# FPGA_IO.net
KiCad netlist of a schematic drawn in Altium Designer
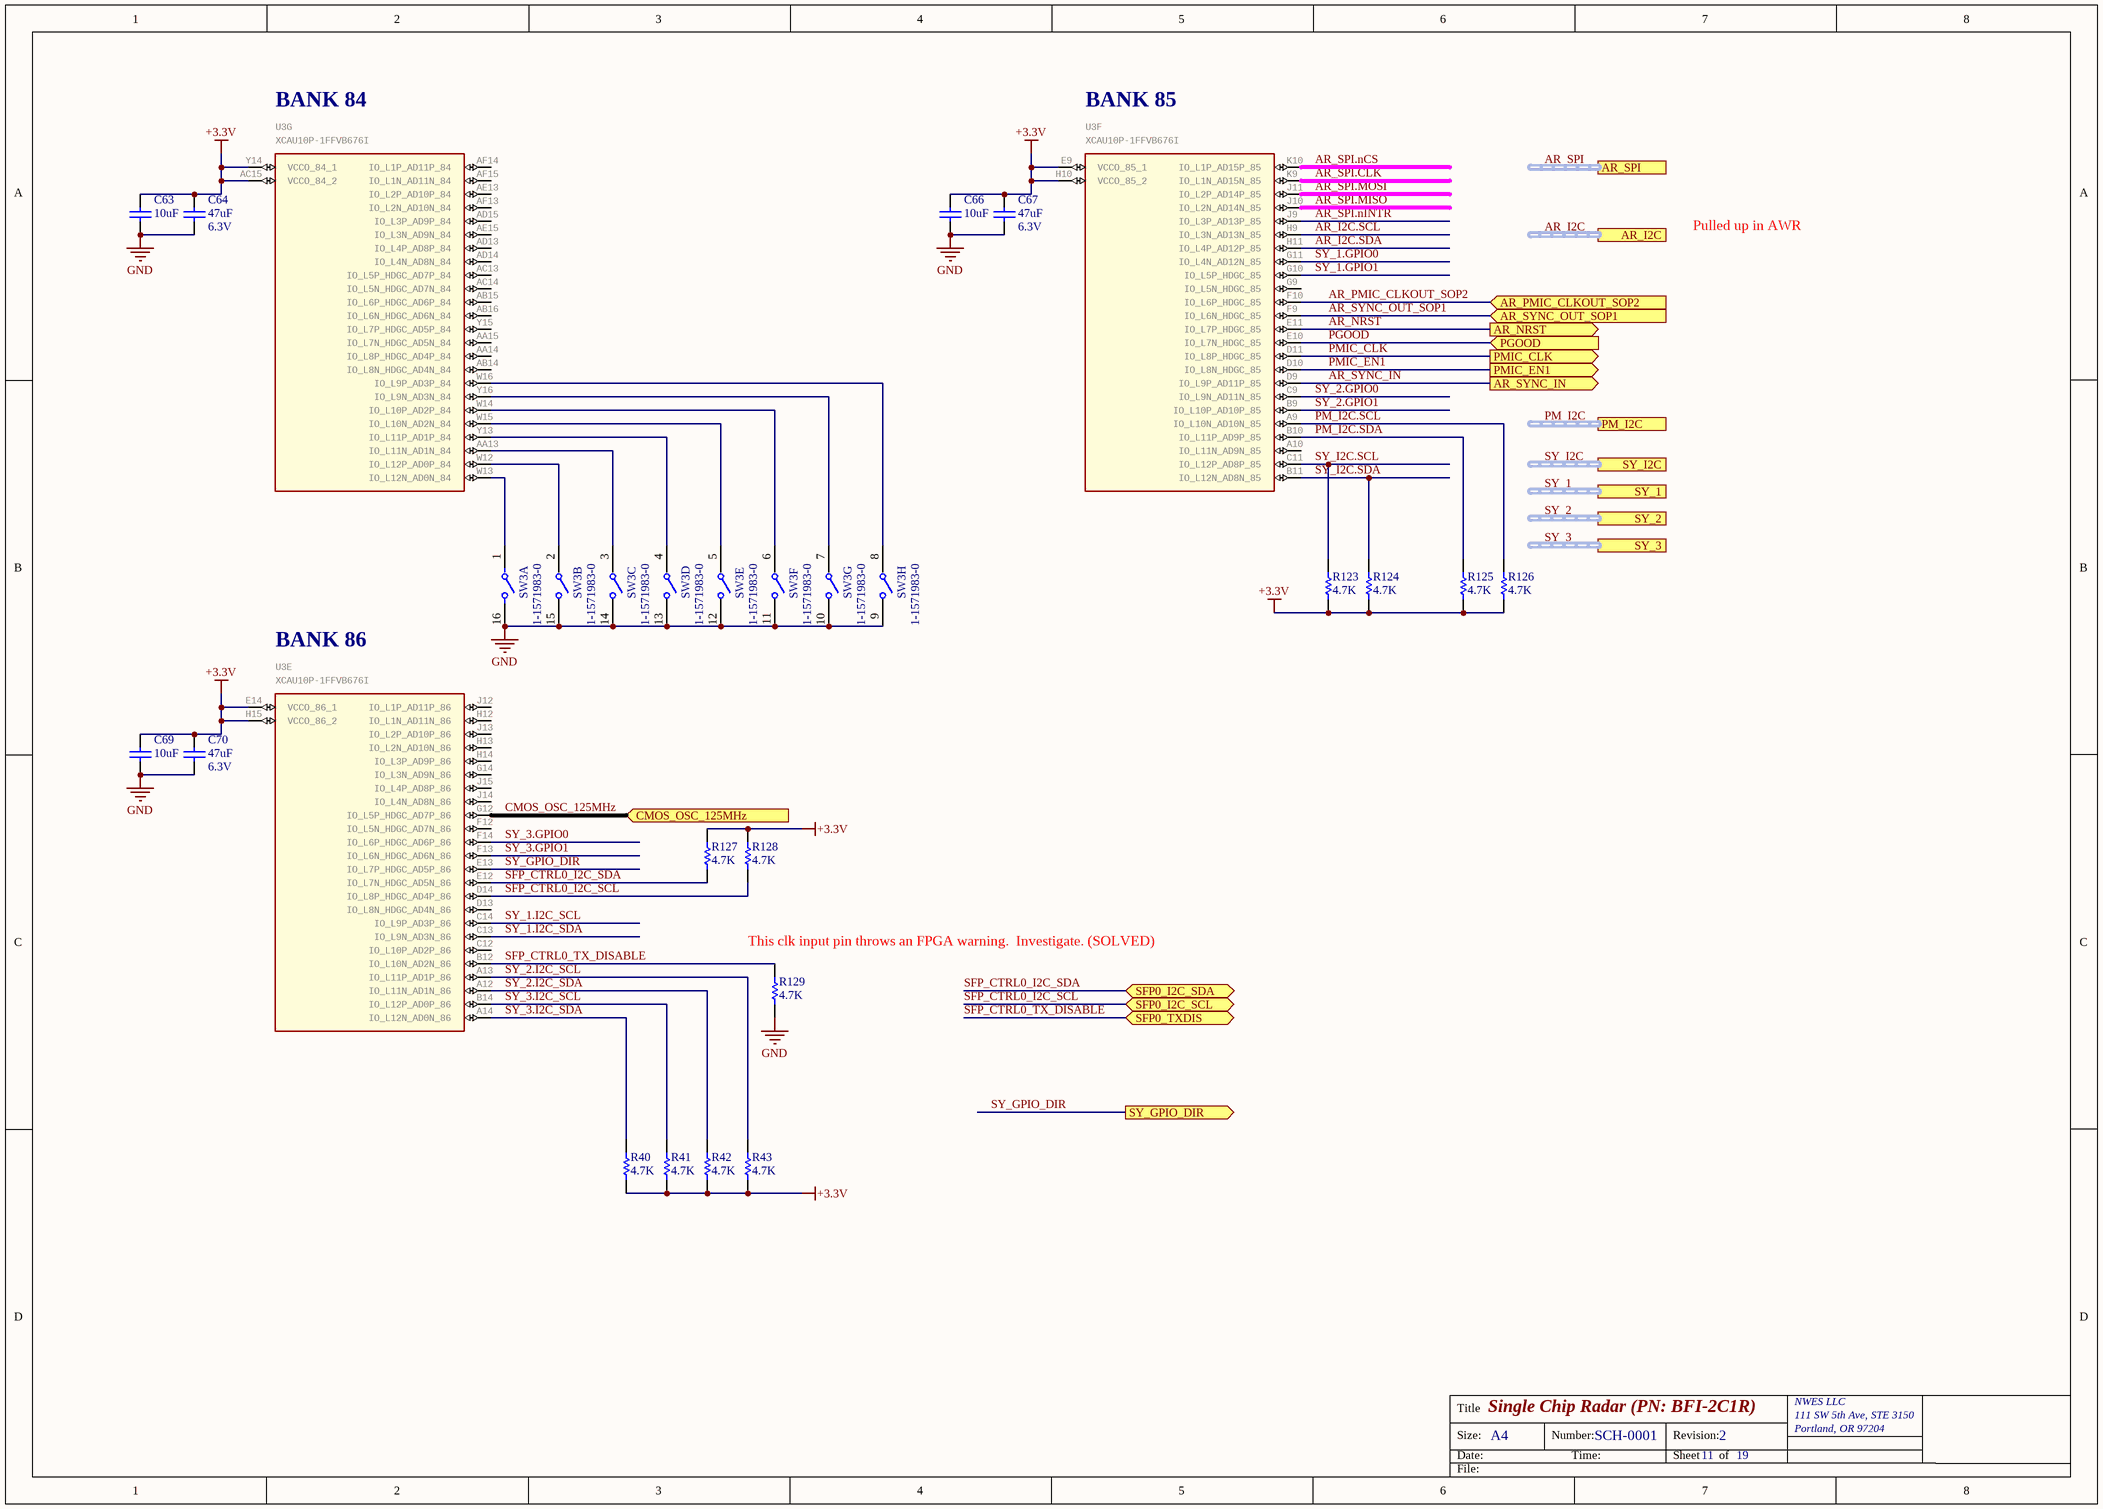
[diagram p0: FPGA IO.SchDoc]

(export (version "E")
  (design (tool "Eeschema 10.0.6"))
  (components
    (comp (ref "C63")
      (value "10uF")
      (footprint "CAPC1005X90")
      (description "CAP CER 10UF 10V X5R 0402")
      (fields
        (field (name "MANUFACTURER PART NUMBER") "CL05A106MP8NUB8")
        (field (name "MANUFACTURER") "Samsung Electro-Mechanics")
      )
      (libsource (lib "Radar FPGA RF") (part "CAP CER 10UF 10V X5R 0402"))
    )
    (comp (ref "C64")
      (value "47uF")
      (footprint "CAPC2012X145USR")
      (description "CAP CER 47UF 6.3V X5R 0805")
      (fields
        (field (name "MANUFACTURER") "Samsung")
        (field (name "MANUFACTURER PART NUMBER") "CL21A476MQYNNNE")
        (field (name "VOLTAGE RATING") "6.3V")
      )
      (libsource (lib "Radar FPGA RF") (part "CAP CER 47UF 6.3V X5R 0805"))
    )
    (comp (ref "C66")
      (value "10uF")
      (footprint "CAPC1005X90")
      (description "CAP CER 10UF 10V X5R 0402")
      (fields
        (field (name "MANUFACTURER PART NUMBER") "CL05A106MP8NUB8")
        (field (name "MANUFACTURER") "Samsung Electro-Mechanics")
      )
      (libsource (lib "Radar FPGA RF") (part "CAP CER 10UF 10V X5R 0402"))
    )
    (comp (ref "C67")
      (value "47uF")
      (footprint "CAPC2012X145USR")
      (description "CAP CER 47UF 6.3V X5R 0805")
      (fields
        (field (name "MANUFACTURER") "Samsung")
        (field (name "MANUFACTURER PART NUMBER") "CL21A476MQYNNNE")
        (field (name "VOLTAGE RATING") "6.3V")
      )
      (libsource (lib "Radar FPGA RF") (part "CAP CER 47UF 6.3V X5R 0805"))
    )
    (comp (ref "C69")
      (value "10uF")
      (footprint "CAPC1005X90")
      (description "CAP CER 10UF 10V X5R 0402")
      (fields
        (field (name "MANUFACTURER PART NUMBER") "CL05A106MP8NUB8")
        (field (name "MANUFACTURER") "Samsung Electro-Mechanics")
      )
      (libsource (lib "Radar FPGA RF") (part "CAP CER 10UF 10V X5R 0402"))
    )
    (comp (ref "C70")
      (value "47uF")
      (footprint "CAPC2012X145USR")
      (description "CAP CER 47UF 6.3V X5R 0805")
      (fields
        (field (name "MANUFACTURER") "Samsung")
        (field (name "MANUFACTURER PART NUMBER") "CL21A476MQYNNNE")
        (field (name "VOLTAGE RATING") "6.3V")
      )
      (libsource (lib "Radar FPGA RF") (part "CAP CER 47UF 6.3V X5R 0805"))
    )
    (comp (ref "R40")
      (value "4.7K")
      (footprint "RESC1005X40USR")
      (description "RES 4.7K OHM 1% 1/16W 0402")
      (fields
        (field (name "MANUFACTURER") "YAGEO")
        (field (name "MANUFACTURER PART NUMBER") "RC0402FR-074K7L")
      )
      (libsource (lib "SingleChip-Rev2") (part "RES 4.7K OHM 1% 1/16W 0402"))
    )
    (comp (ref "R41")
      (value "4.7K")
      (footprint "RESC1005X40USR")
      (description "RES 4.7K OHM 1% 1/16W 0402")
      (fields
        (field (name "MANUFACTURER") "YAGEO")
        (field (name "MANUFACTURER PART NUMBER") "RC0402FR-074K7L")
      )
      (libsource (lib "SingleChip-Rev2") (part "RES 4.7K OHM 1% 1/16W 0402"))
    )
    (comp (ref "R42")
      (value "4.7K")
      (footprint "RESC1005X40USR")
      (description "RES 4.7K OHM 1% 1/16W 0402")
      (fields
        (field (name "MANUFACTURER") "YAGEO")
        (field (name "MANUFACTURER PART NUMBER") "RC0402FR-074K7L")
      )
      (libsource (lib "SingleChip-Rev2") (part "RES 4.7K OHM 1% 1/16W 0402"))
    )
    (comp (ref "R43")
      (value "4.7K")
      (footprint "RESC1005X40USR")
      (description "RES 4.7K OHM 1% 1/16W 0402")
      (fields
        (field (name "MANUFACTURER") "YAGEO")
        (field (name "MANUFACTURER PART NUMBER") "RC0402FR-074K7L")
      )
      (libsource (lib "SingleChip-Rev2") (part "RES 4.7K OHM 1% 1/16W 0402"))
    )
    (comp (ref "R123")
      (value "4.7K")
      (footprint "RESC1005X40USR")
      (description "RES 4.7K OHM 1% 1/16W 0402")
      (fields
        (field (name "MANUFACTURER") "YAGEO")
        (field (name "MANUFACTURER PART NUMBER") "RC0402FR-074K7L")
      )
      (libsource (lib "Radar FPGA RF") (part "RES 4.7K OHM 1% 1/16W 0402"))
    )
    (comp (ref "R124")
      (value "4.7K")
      (footprint "RESC1005X40USR")
      (description "RES 4.7K OHM 1% 1/16W 0402")
      (fields
        (field (name "MANUFACTURER") "YAGEO")
        (field (name "MANUFACTURER PART NUMBER") "RC0402FR-074K7L")
      )
      (libsource (lib "Radar FPGA RF") (part "RES 4.7K OHM 1% 1/16W 0402"))
    )
    (comp (ref "R125")
      (value "4.7K")
      (footprint "RESC1005X40USR")
      (description "RES 4.7K OHM 1% 1/16W 0402")
      (fields
        (field (name "MANUFACTURER") "YAGEO")
        (field (name "MANUFACTURER PART NUMBER") "RC0402FR-074K7L")
      )
      (libsource (lib "Radar FPGA RF") (part "RES 4.7K OHM 1% 1/16W 0402"))
    )
    (comp (ref "R126")
      (value "4.7K")
      (footprint "RESC1005X40USR")
      (description "RES 4.7K OHM 1% 1/16W 0402")
      (fields
        (field (name "MANUFACTURER") "YAGEO")
        (field (name "MANUFACTURER PART NUMBER") "RC0402FR-074K7L")
      )
      (libsource (lib "Radar FPGA RF") (part "RES 4.7K OHM 1% 1/16W 0402"))
    )
    (comp (ref "R127")
      (value "4.7K")
      (footprint "RESC1005X40USR")
      (description "RES 4.7K OHM 1% 1/16W 0402")
      (fields
        (field (name "MANUFACTURER") "YAGEO")
        (field (name "MANUFACTURER PART NUMBER") "RC0402FR-074K7L")
      )
      (libsource (lib "Radar FPGA RF") (part "RES 4.7K OHM 1% 1/16W 0402"))
    )
    (comp (ref "R128")
      (value "4.7K")
      (footprint "RESC1005X40USR")
      (description "RES 4.7K OHM 1% 1/16W 0402")
      (fields
        (field (name "MANUFACTURER") "YAGEO")
        (field (name "MANUFACTURER PART NUMBER") "RC0402FR-074K7L")
      )
      (libsource (lib "Radar FPGA RF") (part "RES 4.7K OHM 1% 1/16W 0402"))
    )
    (comp (ref "R129")
      (value "4.7K")
      (footprint "RESC1005X40USR")
      (description "RES 4.7K OHM 1% 1/16W 0402")
      (fields
        (field (name "MANUFACTURER") "YAGEO")
        (field (name "MANUFACTURER PART NUMBER") "RC0402FR-074K7L")
      )
      (libsource (lib "Radar FPGA RF") (part "RES 4.7K OHM 1% 1/16W 0402"))
    )
    (comp (ref "SW3")
      (value "1-1571983-0")
      (footprint "FP-1-1571983-0-MFG")
      (description "SWITCH SLIDE DIP SPST 25MA 24V")
      (fields
        (field (name "MANUFACTURER") "TE Connectivity")
        (field (name "OCTOPART") "https://octopart.com/1-1571983-0-te+connectivity-46507283")
      )
      (libsource (lib "Altium Content Vault") (part "b1c630a2f26d6f55c46b66680387f8a"))
    )
    (comp (ref "U3")
      (value "XCAU10P-1FFVB676I")
      (footprint "676-FCBGA (27x27)")
      (description "IC FPGA ARTIXUP 676BGA")
      (fields (field (name "MANUFACTURER") "AMD Xilinx"))
      (libsource (lib "LL") (part "XCAU10P-1FFVB676I"))
    )
  )
  (nets
    (net (code "8") (name "+3.3V") (class "Default")
      (node (ref "C63") (pin "2") (pinfunction "2_2") (pintype "passive"))
      (node (ref "C64") (pin "1") (pinfunction "1_1") (pintype "passive"))
      (node (ref "C66") (pin "2") (pinfunction "2_2") (pintype "passive"))
      (node (ref "C67") (pin "1") (pinfunction "1_1") (pintype "passive"))
      (node (ref "C69") (pin "2") (pinfunction "2_2") (pintype "passive"))
      (node (ref "C70") (pin "1") (pinfunction "1_1") (pintype "passive"))
      (node (ref "R123") (pin "1") (pinfunction "1_1") (pintype "passive"))
      (node (ref "R124") (pin "1") (pinfunction "1_1") (pintype "passive"))
      (node (ref "R125") (pin "1") (pinfunction "1_1") (pintype "passive"))
      (node (ref "R126") (pin "1") (pinfunction "1_1") (pintype "passive"))
      (node (ref "R127") (pin "1") (pinfunction "1_1") (pintype "passive"))
      (node (ref "R128") (pin "1") (pinfunction "1_1") (pintype "passive"))
      (node (ref "R40") (pin "2") (pinfunction "2_2") (pintype "passive"))
      (node (ref "R41") (pin "2") (pinfunction "2_2") (pintype "passive"))
      (node (ref "R42") (pin "2") (pinfunction "2_2") (pintype "passive"))
      (node (ref "R43") (pin "2") (pinfunction "2_2") (pintype "passive"))
      (node (ref "U3") (pin "AC15") (pinfunction "VCCO_84_2_AC15") (pintype "bidirectional"))
      (node (ref "U3") (pin "E14") (pinfunction "VCCO_86_1_E14") (pintype "bidirectional"))
      (node (ref "U3") (pin "E9") (pinfunction "VCCO_85_1_E9") (pintype "bidirectional"))
      (node (ref "U3") (pin "H10") (pinfunction "VCCO_85_2_H10") (pintype "bidirectional"))
      (node (ref "U3") (pin "H15") (pinfunction "VCCO_86_2_H15") (pintype "bidirectional"))
      (node (ref "U3") (pin "Y14") (pinfunction "VCCO_84_1_Y14") (pintype "bidirectional"))
    )
    (net (code "9") (name "/AR_I2C.SCL") (class "Default")
      (node (ref "U3") (pin "H9") (pinfunction "IO_L3N_AD13N_85_H9") (pintype "bidirectional"))
    )
    (net (code "10") (name "/AR_I2C.SDA") (class "Default")
      (node (ref "U3") (pin "H11") (pinfunction "IO_L4P_AD12P_85_H11") (pintype "bidirectional"))
    )
    (net (code "11") (name "/AR_NRST") (class "Default")
      (node (ref "U3") (pin "E11") (pinfunction "IO_L7P_HDGC_85_E11") (pintype "bidirectional"))
    )
    (net (code "12") (name "/AR_PMIC_CLKOUT_SOP2") (class "Default")
      (node (ref "U3") (pin "F10") (pinfunction "IO_L6P_HDGC_85_F10") (pintype "bidirectional"))
    )
    (net (code "13") (name "/AR_SPI.CLK") (class "Default")
      (node (ref "U3") (pin "K9") (pinfunction "IO_L1N_AD15N_85_K9") (pintype "bidirectional"))
    )
    (net (code "14") (name "/AR_SPI.MISO") (class "Default")
      (node (ref "U3") (pin "J10") (pinfunction "IO_L2N_AD14N_85_J10") (pintype "bidirectional"))
    )
    (net (code "15") (name "/AR_SPI.MOSI") (class "Default")
      (node (ref "U3") (pin "J11") (pinfunction "IO_L2P_AD14P_85_J11") (pintype "bidirectional"))
    )
    (net (code "16") (name "/AR_SPI.nCS") (class "Default")
      (node (ref "U3") (pin "K10") (pinfunction "IO_L1P_AD15P_85_K10") (pintype "bidirectional"))
    )
    (net (code "17") (name "/AR_SPI.nINTR") (class "Default")
      (node (ref "U3") (pin "J9") (pinfunction "IO_L3P_AD13P_85_J9") (pintype "bidirectional"))
    )
    (net (code "18") (name "/AR_SYNC_IN") (class "Default")
      (node (ref "U3") (pin "D9") (pinfunction "IO_L9P_AD11P_85_D9") (pintype "bidirectional"))
    )
    (net (code "19") (name "/AR_SYNC_OUT_SOP1") (class "Default")
      (node (ref "U3") (pin "F9") (pinfunction "IO_L6N_HDGC_85_F9") (pintype "bidirectional"))
    )
    (net (code "20") (name "/CMOS_OSC_125MHz") (class "Default")
      (node (ref "U3") (pin "G12") (pinfunction "IO_L5P_HDGC_AD7P_86_G12") (pintype "bidirectional"))
    )
    (net (code "21") (name "/PGOOD") (class "Default")
      (node (ref "U3") (pin "E10") (pinfunction "IO_L7N_HDGC_85_E10") (pintype "bidirectional"))
    )
    (net (code "22") (name "/PMIC_CLK") (class "Default")
      (node (ref "U3") (pin "D11") (pinfunction "IO_L8P_HDGC_85_D11") (pintype "bidirectional"))
    )
    (net (code "23") (name "/PMIC_EN1") (class "Default")
      (node (ref "U3") (pin "D10") (pinfunction "IO_L8N_HDGC_85_D10") (pintype "bidirectional"))
    )
    (net (code "24") (name "/PM_I2C.SCL") (class "Default")
      (node (ref "R126") (pin "2") (pinfunction "2_2") (pintype "passive"))
      (node (ref "U3") (pin "A9") (pinfunction "IO_L10N_AD10N_85_A9") (pintype "bidirectional"))
    )
    (net (code "25") (name "/PM_I2C.SDA") (class "Default")
      (node (ref "R125") (pin "2") (pinfunction "2_2") (pintype "passive"))
      (node (ref "U3") (pin "B10") (pinfunction "IO_L11P_AD9P_85_B10") (pintype "bidirectional"))
    )
    (net (code "26") (name "/SFP_CTRL0_I2C_SCL") (class "Default")
      (node (ref "R128") (pin "2") (pinfunction "2_2") (pintype "passive"))
      (node (ref "U3") (pin "D14") (pinfunction "IO_L8P_HDGC_AD4P_86_D14") (pintype "bidirectional"))
    )
    (net (code "27") (name "/SFP_CTRL0_I2C_SDA") (class "Default")
      (node (ref "R127") (pin "2") (pinfunction "2_2") (pintype "passive"))
      (node (ref "U3") (pin "E12") (pinfunction "IO_L7N_HDGC_AD5N_86_E12") (pintype "bidirectional"))
    )
    (net (code "28") (name "/SFP_CTRL0_TX_DISABLE") (class "Default")
      (node (ref "R129") (pin "1") (pinfunction "1_1") (pintype "passive"))
      (node (ref "U3") (pin "B12") (pinfunction "IO_L10N_AD2N_86_B12") (pintype "bidirectional"))
    )
    (net (code "29") (name "/SY_1.GPIO0") (class "Default")
      (node (ref "U3") (pin "G11") (pinfunction "IO_L4N_AD12N_85_G11") (pintype "bidirectional"))
    )
    (net (code "30") (name "/SY_1.GPIO1") (class "Default")
      (node (ref "U3") (pin "G10") (pinfunction "IO_L5P_HDGC_85_G10") (pintype "bidirectional"))
    )
    (net (code "31") (name "/SY_1.I2C_SCL") (class "Default")
      (node (ref "U3") (pin "C14") (pinfunction "IO_L9P_AD3P_86_C14") (pintype "bidirectional"))
    )
    (net (code "32") (name "/SY_1.I2C_SDA") (class "Default")
      (node (ref "U3") (pin "C13") (pinfunction "IO_L9N_AD3N_86_C13") (pintype "bidirectional"))
    )
    (net (code "33") (name "/SY_2.GPIO0") (class "Default")
      (node (ref "U3") (pin "C9") (pinfunction "IO_L9N_AD11N_85_C9") (pintype "bidirectional"))
    )
    (net (code "34") (name "/SY_2.GPIO1") (class "Default")
      (node (ref "U3") (pin "B9") (pinfunction "IO_L10P_AD10P_85_B9") (pintype "bidirectional"))
    )
    (net (code "35") (name "/SY_2.I2C_SCL") (class "Default")
      (node (ref "R43") (pin "1") (pinfunction "1_1") (pintype "passive"))
      (node (ref "U3") (pin "A13") (pinfunction "IO_L11P_AD1P_86_A13") (pintype "bidirectional"))
    )
    (net (code "36") (name "/SY_2.I2C_SDA") (class "Default")
      (node (ref "R42") (pin "1") (pinfunction "1_1") (pintype "passive"))
      (node (ref "U3") (pin "A12") (pinfunction "IO_L11N_AD1N_86_A12") (pintype "bidirectional"))
    )
    (net (code "37") (name "/SY_3.GPIO0") (class "Default")
      (node (ref "U3") (pin "F14") (pinfunction "IO_L6P_HDGC_AD6P_86_F14") (pintype "bidirectional"))
    )
    (net (code "38") (name "/SY_3.GPIO1") (class "Default")
      (node (ref "U3") (pin "F13") (pinfunction "IO_L6N_HDGC_AD6N_86_F13") (pintype "bidirectional"))
    )
    (net (code "39") (name "/SY_3.I2C_SCL") (class "Default")
      (node (ref "R41") (pin "1") (pinfunction "1_1") (pintype "passive"))
      (node (ref "U3") (pin "B14") (pinfunction "IO_L12P_AD0P_86_B14") (pintype "bidirectional"))
    )
    (net (code "40") (name "/SY_3.I2C_SDA") (class "Default")
      (node (ref "R40") (pin "1") (pinfunction "1_1") (pintype "passive"))
      (node (ref "U3") (pin "A14") (pinfunction "IO_L12N_AD0N_86_A14") (pintype "bidirectional"))
    )
    (net (code "41") (name "/SY_GPIO_DIR") (class "Default")
      (node (ref "U3") (pin "E13") (pinfunction "IO_L7P_HDGC_AD5P_86_E13") (pintype "bidirectional"))
    )
    (net (code "42") (name "/SY_I2C.SCL") (class "Default")
      (node (ref "R123") (pin "2") (pinfunction "2_2") (pintype "passive"))
      (node (ref "U3") (pin "C11") (pinfunction "IO_L12P_AD8P_85_C11") (pintype "bidirectional"))
    )
    (net (code "43") (name "/SY_I2C.SDA") (class "Default")
      (node (ref "R124") (pin "2") (pinfunction "2_2") (pintype "passive"))
      (node (ref "U3") (pin "B11") (pinfunction "IO_L12N_AD8N_85_B11") (pintype "bidirectional"))
    )
    (net (code "51") (name "GND") (class "Default")
      (node (ref "C63") (pin "1") (pinfunction "1_1") (pintype "passive"))
      (node (ref "C64") (pin "2") (pinfunction "2_2") (pintype "passive"))
      (node (ref "C66") (pin "1") (pinfunction "1_1") (pintype "passive"))
      (node (ref "C67") (pin "2") (pinfunction "2_2") (pintype "passive"))
      (node (ref "C69") (pin "1") (pinfunction "1_1") (pintype "passive"))
      (node (ref "C70") (pin "2") (pinfunction "2_2") (pintype "passive"))
      (node (ref "R129") (pin "2") (pinfunction "2_2") (pintype "passive"))
      (node (ref "SW3") (pin "10") (pinfunction "10_10") (pintype "passive"))
      (node (ref "SW3") (pin "11") (pinfunction "11_11") (pintype "passive"))
      (node (ref "SW3") (pin "12") (pinfunction "12_12") (pintype "passive"))
      (node (ref "SW3") (pin "13") (pinfunction "13_13") (pintype "passive"))
      (node (ref "SW3") (pin "14") (pinfunction "14_14") (pintype "passive"))
      (node (ref "SW3") (pin "15") (pinfunction "15_15") (pintype "passive"))
      (node (ref "SW3") (pin "16") (pinfunction "16_16") (pintype "passive"))
      (node (ref "SW3") (pin "9") (pinfunction "9_9") (pintype "passive"))
    )
    (net (code "52") (name "Net-(U3G-IO_L9N_AD3N_84)") (class "Default")
      (node (ref "SW3") (pin "7") (pinfunction "7_7") (pintype "passive"))
      (node (ref "U3") (pin "Y16") (pinfunction "IO_L9N_AD3N_84_Y16") (pintype "bidirectional"))
    )
    (net (code "53") (name "Net-(U3G-IO_L9P_AD3P_84)") (class "Default")
      (node (ref "SW3") (pin "8") (pinfunction "8_8") (pintype "passive"))
      (node (ref "U3") (pin "W16") (pinfunction "IO_L9P_AD3P_84_W16") (pintype "bidirectional"))
    )
    (net (code "54") (name "Net-(U3G-IO_L10N_AD2N_84)") (class "Default")
      (node (ref "SW3") (pin "5") (pinfunction "5_5") (pintype "passive"))
      (node (ref "U3") (pin "W15") (pinfunction "IO_L10N_AD2N_84_W15") (pintype "bidirectional"))
    )
    (net (code "55") (name "Net-(U3G-IO_L10P_AD2P_84)") (class "Default")
      (node (ref "SW3") (pin "6") (pinfunction "6_6") (pintype "passive"))
      (node (ref "U3") (pin "W14") (pinfunction "IO_L10P_AD2P_84_W14") (pintype "bidirectional"))
    )
    (net (code "56") (name "Net-(U3G-IO_L11N_AD1N_84)") (class "Default")
      (node (ref "SW3") (pin "3") (pinfunction "3_3") (pintype "passive"))
      (node (ref "U3") (pin "AA13") (pinfunction "IO_L11N_AD1N_84_AA13") (pintype "bidirectional"))
    )
    (net (code "57") (name "Net-(U3G-IO_L11P_AD1P_84)") (class "Default")
      (node (ref "SW3") (pin "4") (pinfunction "4_4") (pintype "passive"))
      (node (ref "U3") (pin "Y13") (pinfunction "IO_L11P_AD1P_84_Y13") (pintype "bidirectional"))
    )
    (net (code "58") (name "Net-(U3G-IO_L12N_AD0N_84)") (class "Default")
      (node (ref "SW3") (pin "1") (pinfunction "1_1") (pintype "passive"))
      (node (ref "U3") (pin "W13") (pinfunction "IO_L12N_AD0N_84_W13") (pintype "bidirectional"))
    )
    (net (code "59") (name "Net-(U3G-IO_L12P_AD0P_84)") (class "Default")
      (node (ref "SW3") (pin "2") (pinfunction "2_2") (pintype "passive"))
      (node (ref "U3") (pin "W12") (pinfunction "IO_L12P_AD0P_84_W12") (pintype "bidirectional"))
    )
    (net (code "60") (name "unconnected-(U3E-IO_L1N_AD11N_86-PadH12)") (class "Default")
      (node (ref "U3") (pin "H12") (pinfunction "IO_L1N_AD11N_86_H12") (pintype "bidirectional"))
    )
    (net (code "61") (name "unconnected-(U3E-IO_L1P_AD11P_86-PadJ12)") (class "Default")
      (node (ref "U3") (pin "J12") (pinfunction "IO_L1P_AD11P_86_J12") (pintype "bidirectional"))
    )
    (net (code "62") (name "unconnected-(U3E-IO_L2N_AD10N_86-PadH13)") (class "Default")
      (node (ref "U3") (pin "H13") (pinfunction "IO_L2N_AD10N_86_H13") (pintype "bidirectional"))
    )
    (net (code "63") (name "unconnected-(U3E-IO_L2P_AD10P_86-PadJ13)") (class "Default")
      (node (ref "U3") (pin "J13") (pinfunction "IO_L2P_AD10P_86_J13") (pintype "bidirectional"))
    )
    (net (code "64") (name "unconnected-(U3E-IO_L3N_AD9N_86-PadG14)") (class "Default")
      (node (ref "U3") (pin "G14") (pinfunction "IO_L3N_AD9N_86_G14") (pintype "bidirectional"))
    )
    (net (code "65") (name "unconnected-(U3E-IO_L3P_AD9P_86-PadH14)") (class "Default")
      (node (ref "U3") (pin "H14") (pinfunction "IO_L3P_AD9P_86_H14") (pintype "bidirectional"))
    )
    (net (code "66") (name "unconnected-(U3E-IO_L4N_AD8N_86-PadJ14)") (class "Default")
      (node (ref "U3") (pin "J14") (pinfunction "IO_L4N_AD8N_86_J14") (pintype "bidirectional"))
    )
    (net (code "67") (name "unconnected-(U3E-IO_L4P_AD8P_86-PadJ15)") (class "Default")
      (node (ref "U3") (pin "J15") (pinfunction "IO_L4P_AD8P_86_J15") (pintype "bidirectional"))
    )
    (net (code "68") (name "unconnected-(U3E-IO_L5N_HDGC_AD7N_86-PadF12)") (class "Default")
      (node (ref "U3") (pin "F12") (pinfunction "IO_L5N_HDGC_AD7N_86_F12") (pintype "bidirectional"))
    )
    (net (code "69") (name "unconnected-(U3E-IO_L8N_HDGC_AD4N_86-PadD13)") (class "Default")
      (node (ref "U3") (pin "D13") (pinfunction "IO_L8N_HDGC_AD4N_86_D13") (pintype "bidirectional"))
    )
    (net (code "70") (name "unconnected-(U3E-IO_L10P_AD2P_86-PadC12)") (class "Default")
      (node (ref "U3") (pin "C12") (pinfunction "IO_L10P_AD2P_86_C12") (pintype "bidirectional"))
    )
    (net (code "71") (name "unconnected-(U3F-IO_L5N_HDGC_85-PadG9)") (class "Default")
      (node (ref "U3") (pin "G9") (pinfunction "IO_L5N_HDGC_85_G9") (pintype "bidirectional"))
    )
    (net (code "72") (name "unconnected-(U3F-IO_L11N_AD9N_85-PadA10)") (class "Default")
      (node (ref "U3") (pin "A10") (pinfunction "IO_L11N_AD9N_85_A10") (pintype "bidirectional"))
    )
    (net (code "73") (name "unconnected-(U3G-IO_L1N_AD11N_84-PadAF15)") (class "Default")
      (node (ref "U3") (pin "AF15") (pinfunction "IO_L1N_AD11N_84_AF15") (pintype "bidirectional"))
    )
    (net (code "74") (name "unconnected-(U3G-IO_L1P_AD11P_84-PadAF14)") (class "Default")
      (node (ref "U3") (pin "AF14") (pinfunction "IO_L1P_AD11P_84_AF14") (pintype "bidirectional"))
    )
    (net (code "75") (name "unconnected-(U3G-IO_L2N_AD10N_84-PadAF13)") (class "Default")
      (node (ref "U3") (pin "AF13") (pinfunction "IO_L2N_AD10N_84_AF13") (pintype "bidirectional"))
    )
    (net (code "76") (name "unconnected-(U3G-IO_L2P_AD10P_84-PadAE13)") (class "Default")
      (node (ref "U3") (pin "AE13") (pinfunction "IO_L2P_AD10P_84_AE13") (pintype "bidirectional"))
    )
    (net (code "77") (name "unconnected-(U3G-IO_L3N_AD9N_84-PadAE15)") (class "Default")
      (node (ref "U3") (pin "AE15") (pinfunction "IO_L3N_AD9N_84_AE15") (pintype "bidirectional"))
    )
    (net (code "78") (name "unconnected-(U3G-IO_L3P_AD9P_84-PadAD15)") (class "Default")
      (node (ref "U3") (pin "AD15") (pinfunction "IO_L3P_AD9P_84_AD15") (pintype "bidirectional"))
    )
    (net (code "79") (name "unconnected-(U3G-IO_L4N_AD8N_84-PadAD14)") (class "Default")
      (node (ref "U3") (pin "AD14") (pinfunction "IO_L4N_AD8N_84_AD14") (pintype "bidirectional"))
    )
    (net (code "80") (name "unconnected-(U3G-IO_L4P_AD8P_84-PadAD13)") (class "Default")
      (node (ref "U3") (pin "AD13") (pinfunction "IO_L4P_AD8P_84_AD13") (pintype "bidirectional"))
    )
    (net (code "81") (name "unconnected-(U3G-IO_L5N_HDGC_AD7N_84-PadAC14)") (class "Default")
      (node (ref "U3") (pin "AC14") (pinfunction "IO_L5N_HDGC_AD7N_84_AC14") (pintype "bidirectional"))
    )
    (net (code "82") (name "unconnected-(U3G-IO_L5P_HDGC_AD7P_84-PadAC13)") (class "Default")
      (node (ref "U3") (pin "AC13") (pinfunction "IO_L5P_HDGC_AD7P_84_AC13") (pintype "bidirectional"))
    )
    (net (code "83") (name "unconnected-(U3G-IO_L6N_HDGC_AD6N_84-PadAB16)") (class "Default")
      (node (ref "U3") (pin "AB16") (pinfunction "IO_L6N_HDGC_AD6N_84_AB16") (pintype "bidirectional"))
    )
    (net (code "84") (name "unconnected-(U3G-IO_L6P_HDGC_AD6P_84-PadAB15)") (class "Default")
      (node (ref "U3") (pin "AB15") (pinfunction "IO_L6P_HDGC_AD6P_84_AB15") (pintype "bidirectional"))
    )
    (net (code "85") (name "unconnected-(U3G-IO_L7N_HDGC_AD5N_84-PadAA15)") (class "Default")
      (node (ref "U3") (pin "AA15") (pinfunction "IO_L7N_HDGC_AD5N_84_AA15") (pintype "bidirectional"))
    )
    (net (code "86") (name "unconnected-(U3G-IO_L7P_HDGC_AD5P_84-PadY15)") (class "Default")
      (node (ref "U3") (pin "Y15") (pinfunction "IO_L7P_HDGC_AD5P_84_Y15") (pintype "bidirectional"))
    )
    (net (code "87") (name "unconnected-(U3G-IO_L8N_HDGC_AD4N_84-PadAB14)") (class "Default")
      (node (ref "U3") (pin "AB14") (pinfunction "IO_L8N_HDGC_AD4N_84_AB14") (pintype "bidirectional"))
    )
    (net (code "88") (name "unconnected-(U3G-IO_L8P_HDGC_AD4P_84-PadAA14)") (class "Default")
      (node (ref "U3") (pin "AA14") (pinfunction "IO_L8P_HDGC_AD4P_84_AA14") (pintype "bidirectional"))
    )
  )
)
